# Schematic.net
KiCad netlist of a schematic drawn in EAGLE
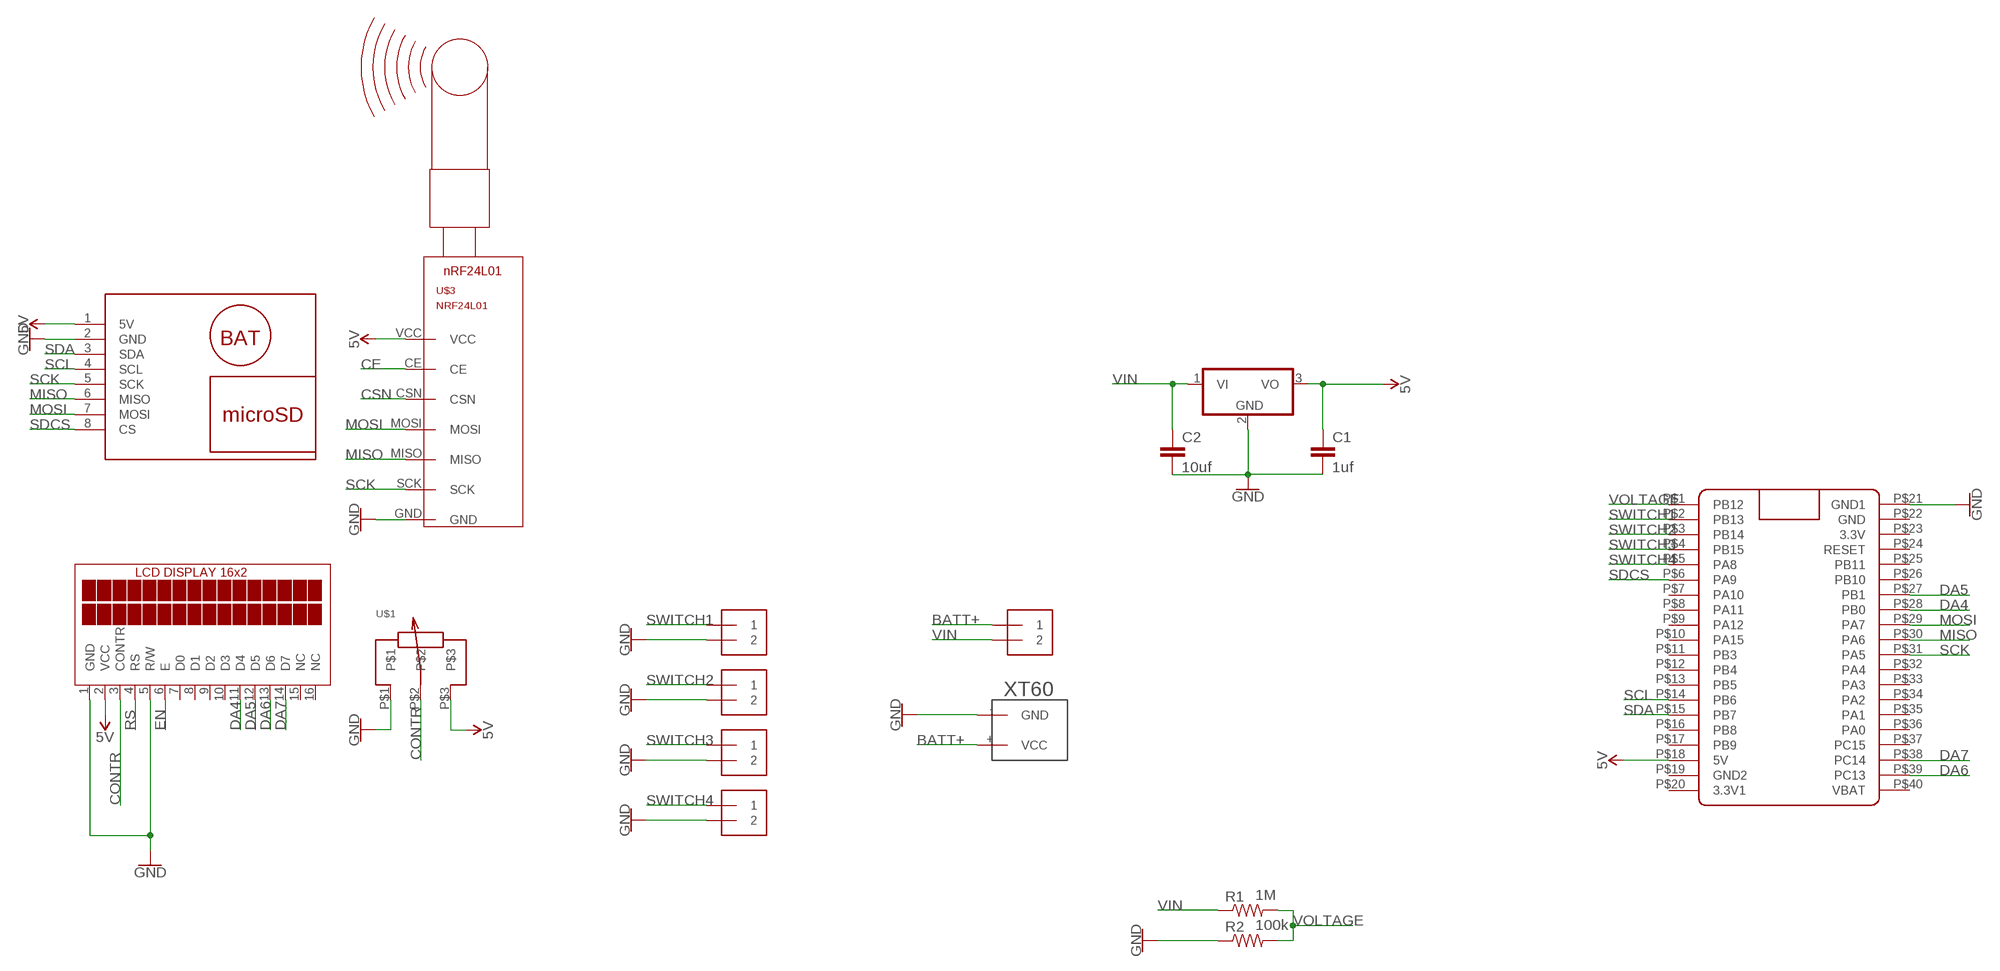
[diagram p0: schematic, sheet 1]

(export (version "E")
  (design (tool "Eeschema 10.0.6"))
  (components
    (comp (ref "C1")
      (value "1uf")
      (footprint "eagle-import:C025-030X050")
      (libsource (lib "eagle-import") (part "C-EU025-030X050"))
    )
    (comp (ref "C2")
      (value "10uf")
      (footprint "eagle-import:C025-030X050")
      (libsource (lib "eagle-import") (part "C-EU025-030X050"))
    )
    (comp (ref "DIS1")
      (value "TUXGR_16X2_R2")
      (footprint "eagle-import:TUXGR_16X2_R2")
      (libsource (lib "eagle-import") (part "TUXGR_16X2_R2"))
    )
    (comp (ref "IC1")
      (value "7805T")
      (footprint "eagle-import:TO220H")
      (libsource (lib "eagle-import") (part "78T05"))
    )
    (comp (ref "J1")
      (value "1X2-3.5MM")
      (footprint "eagle-import:1X2-3.5MM")
      (libsource (lib "eagle-import") (part "1X2-3.5MM"))
    )
    (comp (ref "J2")
      (value "1X2-3.5MM")
      (footprint "eagle-import:1X2-3.5MM")
      (libsource (lib "eagle-import") (part "1X2-3.5MM"))
    )
    (comp (ref "J3")
      (value "1X2-3.5MM")
      (footprint "eagle-import:1X2-3.5MM")
      (libsource (lib "eagle-import") (part "1X2-3.5MM"))
    )
    (comp (ref "J4")
      (value "1X2-3.5MM")
      (footprint "eagle-import:1X2-3.5MM")
      (libsource (lib "eagle-import") (part "1X2-3.5MM"))
    )
    (comp (ref "J5")
      (value "1X2-3.5MM")
      (footprint "eagle-import:1X2-3.5MM")
      (libsource (lib "eagle-import") (part "1X2-3.5MM"))
    )
    (comp (ref "R1")
      (value "1M")
      (footprint "eagle-import:0204_5")
      (libsource (lib "eagle-import") (part "R-US_0204/5"))
    )
    (comp (ref "R2")
      (value "100k")
      (footprint "eagle-import:0204_5")
      (libsource (lib "eagle-import") (part "R-US_0204/5"))
    )
    (comp (ref "U$1")
      (value "POTENTIOMETER")
      (footprint "eagle-import:POTENTIOMETER")
      (libsource (lib "eagle-import") (part "POTENTIOMETER"))
    )
    (comp (ref "U$2")
      (value "XT60")
      (footprint "eagle-import:XT60")
      (libsource (lib "eagle-import") (part "XT60"))
    )
    (comp (ref "U$3")
      (value "NRF24L01")
      (footprint "eagle-import:NRF24L01")
      (libsource (lib "eagle-import") (part "NRF24L01"))
    )
    (comp (ref "U$4")
      (value "DATA-LOGGER-MINI")
      (footprint "eagle-import:DATA-LOGGER-MINI")
      (libsource (lib "eagle-import") (part "DATA-LOGGER-MINI"))
    )
    (comp (ref "U$6")
      (value "BLUE_PILL")
      (footprint "eagle-import:BLUE_PILL")
      (libsource (lib "eagle-import") (part "BLUE_PILL"))
    )
  )
  (nets
    (net (code "1") (name "/BATT+") (class "Default")
      (node (ref "J5") (pin "1") (pinfunction "1_1") (pintype "passive"))
      (node (ref "U$2") (pin "+") (pinfunction "VCC_+") (pintype "bidirectional"))
    )
    (net (code "2") (name "/CE") (class "Default")
      (node (ref "U$3") (pin "CE") (pinfunction "CE_CE") (pintype "bidirectional"))
    )
    (net (code "3") (name "/CONTR") (class "Default")
      (node (ref "DIS1") (pin "3") (pinfunction "CONTR_3") (pintype "input"))
      (node (ref "U$1") (pin "P$2") (pinfunction "P$2_P$2") (pintype "bidirectional"))
    )
    (net (code "4") (name "/CSN") (class "Default")
      (node (ref "U$3") (pin "CSN") (pinfunction "CSN_CSN") (pintype "bidirectional"))
    )
    (net (code "5") (name "/DA4") (class "Default")
      (node (ref "DIS1") (pin "11") (pinfunction "D4_11") (pintype "input"))
      (node (ref "U$6") (pin "P$28") (pinfunction "PB0_P$28") (pintype "bidirectional"))
    )
    (net (code "6") (name "/DA5") (class "Default")
      (node (ref "DIS1") (pin "12") (pinfunction "D5_12") (pintype "input"))
      (node (ref "U$6") (pin "P$27") (pinfunction "PB1_P$27") (pintype "bidirectional"))
    )
    (net (code "7") (name "/DA6") (class "Default")
      (node (ref "DIS1") (pin "13") (pinfunction "D6_13") (pintype "input"))
      (node (ref "U$6") (pin "P$39") (pinfunction "PC13_P$39") (pintype "bidirectional"))
    )
    (net (code "8") (name "/DA7") (class "Default")
      (node (ref "DIS1") (pin "14") (pinfunction "D7_14") (pintype "input"))
      (node (ref "U$6") (pin "P$38") (pinfunction "PC14_P$38") (pintype "bidirectional"))
    )
    (net (code "9") (name "/EN") (class "Default")
      (node (ref "DIS1") (pin "6") (pinfunction "E_6") (pintype "input"))
    )
    (net (code "10") (name "/MISO") (class "Default")
      (node (ref "U$3") (pin "MISO") (pinfunction "MISO_MISO") (pintype "bidirectional"))
      (node (ref "U$4") (pin "6") (pinfunction "MISO_6") (pintype "bidirectional"))
      (node (ref "U$6") (pin "P$30") (pinfunction "PA6_P$30") (pintype "bidirectional"))
    )
    (net (code "11") (name "/MOSI") (class "Default")
      (node (ref "U$3") (pin "MOSI") (pinfunction "MOSI_MOSI") (pintype "bidirectional"))
      (node (ref "U$4") (pin "7") (pinfunction "MOSI_7") (pintype "bidirectional"))
      (node (ref "U$6") (pin "P$29") (pinfunction "PA7_P$29") (pintype "bidirectional"))
    )
    (net (code "12") (name "/RS") (class "Default")
      (node (ref "DIS1") (pin "4") (pinfunction "RS_4") (pintype "input"))
    )
    (net (code "13") (name "/SCK") (class "Default")
      (node (ref "U$3") (pin "SCK") (pinfunction "SCK_SCK") (pintype "bidirectional"))
      (node (ref "U$4") (pin "5") (pinfunction "SCK_5") (pintype "bidirectional"))
      (node (ref "U$6") (pin "P$31") (pinfunction "PA5_P$31") (pintype "bidirectional"))
    )
    (net (code "14") (name "/SCL") (class "Default")
      (node (ref "U$4") (pin "4") (pinfunction "SCL_4") (pintype "bidirectional"))
      (node (ref "U$6") (pin "P$14") (pinfunction "PB6_P$14") (pintype "bidirectional"))
    )
    (net (code "15") (name "/SDA") (class "Default")
      (node (ref "U$4") (pin "3") (pinfunction "SDA_3") (pintype "bidirectional"))
      (node (ref "U$6") (pin "P$15") (pinfunction "PB7_P$15") (pintype "bidirectional"))
    )
    (net (code "16") (name "/SDCS") (class "Default")
      (node (ref "U$4") (pin "8") (pinfunction "CS_8") (pintype "power_in"))
      (node (ref "U$6") (pin "P$6") (pinfunction "PA9_P$6") (pintype "bidirectional"))
    )
    (net (code "17") (name "/SWITCH1") (class "Default")
      (node (ref "J1") (pin "1") (pinfunction "1_1") (pintype "passive"))
      (node (ref "U$6") (pin "P$2") (pinfunction "PB13_P$2") (pintype "bidirectional"))
    )
    (net (code "18") (name "/SWITCH2") (class "Default")
      (node (ref "J2") (pin "1") (pinfunction "1_1") (pintype "passive"))
      (node (ref "U$6") (pin "P$3") (pinfunction "PB14_P$3") (pintype "bidirectional"))
    )
    (net (code "19") (name "/SWITCH3") (class "Default")
      (node (ref "J3") (pin "1") (pinfunction "1_1") (pintype "passive"))
      (node (ref "U$6") (pin "P$4") (pinfunction "PB15_P$4") (pintype "bidirectional"))
    )
    (net (code "20") (name "/SWITCH4") (class "Default")
      (node (ref "J4") (pin "1") (pinfunction "1_1") (pintype "passive"))
      (node (ref "U$6") (pin "P$5") (pinfunction "PA8_P$5") (pintype "bidirectional"))
    )
    (net (code "21") (name "/VIN") (class "Default")
      (node (ref "C2") (pin "1") (pinfunction "1_1") (pintype "passive"))
      (node (ref "IC1") (pin "1") (pinfunction "VI_1") (pintype "input"))
      (node (ref "J5") (pin "2") (pinfunction "2_2") (pintype "passive"))
      (node (ref "R1") (pin "1") (pinfunction "1_1") (pintype "passive"))
    )
    (net (code "22") (name "/VOLTAGE") (class "Default")
      (node (ref "R1") (pin "2") (pinfunction "2_2") (pintype "passive"))
      (node (ref "R2") (pin "2") (pinfunction "2_2") (pintype "passive"))
      (node (ref "U$6") (pin "P$1") (pinfunction "PB12_P$1") (pintype "bidirectional"))
    )
    (net (code "23") (name "5V") (class "Default")
      (node (ref "C1") (pin "1") (pinfunction "1_1") (pintype "passive"))
      (node (ref "DIS1") (pin "2") (pinfunction "VCC_2") (pintype "power_in"))
      (node (ref "IC1") (pin "3") (pinfunction "VO_3") (pintype "passive"))
      (node (ref "U$1") (pin "P$3") (pinfunction "P$3_P$3") (pintype "bidirectional"))
      (node (ref "U$3") (pin "VCC") (pinfunction "VCC_VCC") (pintype "bidirectional"))
      (node (ref "U$4") (pin "1") (pinfunction "5V_1") (pintype "power_in"))
      (node (ref "U$6") (pin "P$18") (pinfunction "5V_P$18") (pintype "bidirectional"))
    )
    (net (code "24") (name "GND") (class "Default")
      (node (ref "C1") (pin "2") (pinfunction "2_2") (pintype "passive"))
      (node (ref "C2") (pin "2") (pinfunction "2_2") (pintype "passive"))
      (node (ref "DIS1") (pin "1") (pinfunction "GND_1") (pintype "power_in"))
      (node (ref "DIS1") (pin "5") (pinfunction "R/W_5") (pintype "input"))
      (node (ref "IC1") (pin "2") (pinfunction "GND_2") (pintype "passive"))
      (node (ref "J1") (pin "2") (pinfunction "2_2") (pintype "passive"))
      (node (ref "J2") (pin "2") (pinfunction "2_2") (pintype "passive"))
      (node (ref "J3") (pin "2") (pinfunction "2_2") (pintype "passive"))
      (node (ref "J4") (pin "2") (pinfunction "2_2") (pintype "passive"))
      (node (ref "R2") (pin "1") (pinfunction "1_1") (pintype "passive"))
      (node (ref "U$1") (pin "P$1") (pinfunction "P$1_P$1") (pintype "bidirectional"))
      (node (ref "U$2") (pin "-") (pinfunction "GND_-") (pintype "bidirectional"))
      (node (ref "U$3") (pin "GND") (pinfunction "GND_GND") (pintype "bidirectional"))
      (node (ref "U$4") (pin "2") (pinfunction "GND_2") (pintype "power_in"))
      (node (ref "U$6") (pin "P$21") (pinfunction "GND1_P$21") (pintype "power_in"))
    )
    (net (code "25") (name "unconnected-(DIS1-D0-Pad7)") (class "Default")
      (node (ref "DIS1") (pin "7") (pinfunction "D0_7") (pintype "input"))
    )
    (net (code "26") (name "unconnected-(DIS1-D1-Pad8)") (class "Default")
      (node (ref "DIS1") (pin "8") (pinfunction "D1_8") (pintype "input"))
    )
    (net (code "27") (name "unconnected-(DIS1-D2-Pad9)") (class "Default")
      (node (ref "DIS1") (pin "9") (pinfunction "D2_9") (pintype "input"))
    )
    (net (code "28") (name "unconnected-(DIS1-D3-Pad10)") (class "Default")
      (node (ref "DIS1") (pin "10") (pinfunction "D3_10") (pintype "input"))
    )
    (net (code "29") (name "unconnected-(DIS1-NC-Pad15)") (class "Default")
      (node (ref "DIS1") (pin "15") (pinfunction "NC_15") (pintype "no_connect"))
    )
    (net (code "30") (name "unconnected-(DIS1-NC-Pad16)") (class "Default")
      (node (ref "DIS1") (pin "16") (pinfunction "NC_16") (pintype "no_connect"))
    )
    (net (code "31") (name "unconnected-(U$6-3.3V-PadP$23)") (class "Default")
      (node (ref "U$6") (pin "P$23") (pinfunction "3.3V_P$23") (pintype "bidirectional"))
    )
    (net (code "32") (name "unconnected-(U$6-3.3V1-PadP$20)") (class "Default")
      (node (ref "U$6") (pin "P$20") (pinfunction "3.3V1_P$20") (pintype "bidirectional"))
    )
    (net (code "33") (name "unconnected-(U$6-GND-PadP$22)") (class "Default")
      (node (ref "U$6") (pin "P$22") (pinfunction "GND_P$22") (pintype "bidirectional"))
    )
    (net (code "34") (name "unconnected-(U$6-GND2-PadP$19)") (class "Default")
      (node (ref "U$6") (pin "P$19") (pinfunction "GND2_P$19") (pintype "bidirectional"))
    )
    (net (code "35") (name "unconnected-(U$6-PA0-PadP$36)") (class "Default")
      (node (ref "U$6") (pin "P$36") (pinfunction "PA0_P$36") (pintype "bidirectional"))
    )
    (net (code "36") (name "unconnected-(U$6-PA1-PadP$35)") (class "Default")
      (node (ref "U$6") (pin "P$35") (pinfunction "PA1_P$35") (pintype "bidirectional"))
    )
    (net (code "37") (name "unconnected-(U$6-PA2-PadP$34)") (class "Default")
      (node (ref "U$6") (pin "P$34") (pinfunction "PA2_P$34") (pintype "bidirectional"))
    )
    (net (code "38") (name "unconnected-(U$6-PA3-PadP$33)") (class "Default")
      (node (ref "U$6") (pin "P$33") (pinfunction "PA3_P$33") (pintype "bidirectional"))
    )
    (net (code "39") (name "unconnected-(U$6-PA4-PadP$32)") (class "Default")
      (node (ref "U$6") (pin "P$32") (pinfunction "PA4_P$32") (pintype "bidirectional"))
    )
    (net (code "40") (name "unconnected-(U$6-PA10-PadP$7)") (class "Default")
      (node (ref "U$6") (pin "P$7") (pinfunction "PA10_P$7") (pintype "bidirectional"))
    )
    (net (code "41") (name "unconnected-(U$6-PA11-PadP$8)") (class "Default")
      (node (ref "U$6") (pin "P$8") (pinfunction "PA11_P$8") (pintype "bidirectional"))
    )
    (net (code "42") (name "unconnected-(U$6-PA12-PadP$9)") (class "Default")
      (node (ref "U$6") (pin "P$9") (pinfunction "PA12_P$9") (pintype "bidirectional"))
    )
    (net (code "43") (name "unconnected-(U$6-PA15-PadP$10)") (class "Default")
      (node (ref "U$6") (pin "P$10") (pinfunction "PA15_P$10") (pintype "bidirectional"))
    )
    (net (code "44") (name "unconnected-(U$6-PB3-PadP$11)") (class "Default")
      (node (ref "U$6") (pin "P$11") (pinfunction "PB3_P$11") (pintype "bidirectional"))
    )
    (net (code "45") (name "unconnected-(U$6-PB4-PadP$12)") (class "Default")
      (node (ref "U$6") (pin "P$12") (pinfunction "PB4_P$12") (pintype "bidirectional"))
    )
    (net (code "46") (name "unconnected-(U$6-PB5-PadP$13)") (class "Default")
      (node (ref "U$6") (pin "P$13") (pinfunction "PB5_P$13") (pintype "bidirectional"))
    )
    (net (code "47") (name "unconnected-(U$6-PB8-PadP$16)") (class "Default")
      (node (ref "U$6") (pin "P$16") (pinfunction "PB8_P$16") (pintype "bidirectional"))
    )
    (net (code "48") (name "unconnected-(U$6-PB9-PadP$17)") (class "Default")
      (node (ref "U$6") (pin "P$17") (pinfunction "PB9_P$17") (pintype "bidirectional"))
    )
    (net (code "49") (name "unconnected-(U$6-PB10-PadP$26)") (class "Default")
      (node (ref "U$6") (pin "P$26") (pinfunction "PB10_P$26") (pintype "bidirectional"))
    )
    (net (code "50") (name "unconnected-(U$6-PB11-PadP$25)") (class "Default")
      (node (ref "U$6") (pin "P$25") (pinfunction "PB11_P$25") (pintype "bidirectional"))
    )
    (net (code "51") (name "unconnected-(U$6-PC15-PadP$37)") (class "Default")
      (node (ref "U$6") (pin "P$37") (pinfunction "PC15_P$37") (pintype "bidirectional"))
    )
    (net (code "52") (name "unconnected-(U$6-RESET-PadP$24)") (class "Default")
      (node (ref "U$6") (pin "P$24") (pinfunction "RESET_P$24") (pintype "bidirectional"))
    )
    (net (code "53") (name "unconnected-(U$6-VBAT-PadP$40)") (class "Default")
      (node (ref "U$6") (pin "P$40") (pinfunction "VBAT_P$40") (pintype "bidirectional"))
    )
  )
)
